# receiver_mega8.net
KiCad netlist of a schematic drawn in EAGLE
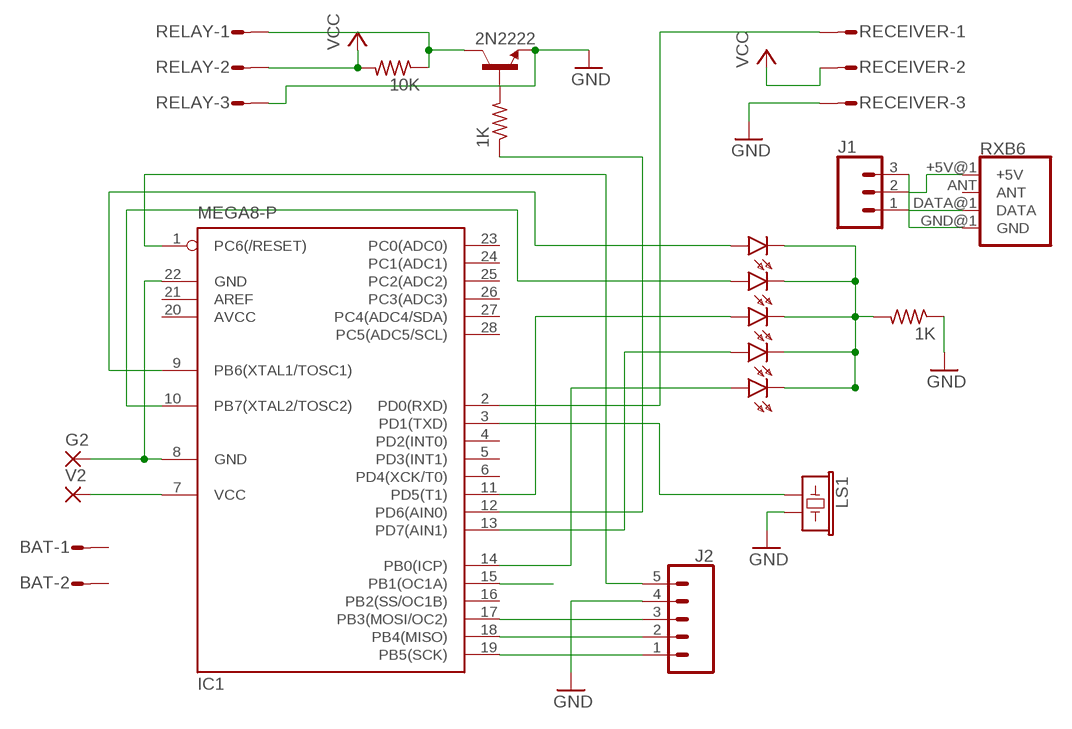
[diagram p0: schematic, sheet 1]

(export (version "E")
  (design (tool "Eeschema 10.0.6"))
  (components
    (comp (ref "BAT")
      (value "S02P")
      (footprint "eagle-import:S02P")
      (libsource (lib "eagle-import") (part "S02P"))
    )
    (comp (ref "D2")
      (value "HLMP6")
      (footprint "eagle-import:HLMP6")
      (fields (field (name "MF") "AGILENT TECHNOLOGIES") (field (name "MPN") "HLMP-6500"))
      (libsource (lib "eagle-import") (part "HLMP6"))
    )
    (comp (ref "D3")
      (value "HLMP6")
      (footprint "eagle-import:HLMP6")
      (fields (field (name "MF") "AGILENT TECHNOLOGIES") (field (name "MPN") "HLMP-6500"))
      (libsource (lib "eagle-import") (part "HLMP6"))
    )
    (comp (ref "D4")
      (value "HLMP6")
      (footprint "eagle-import:HLMP6")
      (fields (field (name "MF") "AGILENT TECHNOLOGIES") (field (name "MPN") "HLMP-6500"))
      (libsource (lib "eagle-import") (part "HLMP6"))
    )
    (comp (ref "D5")
      (value "HLMP6")
      (footprint "eagle-import:HLMP6")
      (fields (field (name "MF") "AGILENT TECHNOLOGIES") (field (name "MPN") "HLMP-6500"))
      (libsource (lib "eagle-import") (part "HLMP6"))
    )
    (comp (ref "D6")
      (value "HLMP6")
      (footprint "eagle-import:HLMP6")
      (fields (field (name "MF") "AGILENT TECHNOLOGIES") (field (name "MPN") "HLMP-6500"))
      (libsource (lib "eagle-import") (part "HLMP6"))
    )
    (comp (ref "G2")
      (value "1,6/0,8")
      (footprint "eagle-import:1,6_0,8")
      (libsource (lib "eagle-import") (part "1,6/0,8"))
    )
    (comp (ref "IC1")
      (value "MEGA8-P")
      (footprint "eagle-import:DIL28-3")
      (libsource (lib "eagle-import") (part "MEGA8-P"))
    )
    (comp (ref "J1")
      (value "CONN_03")
      (footprint "eagle-import:1X03")
      (libsource (lib "eagle-import") (part "CONN_03"))
    )
    (comp (ref "J2")
      (value "CONN_05")
      (footprint "eagle-import:1X05")
      (libsource (lib "eagle-import") (part "CONN_05"))
    )
    (comp (ref "LS1")
      (value "BUZZER-PTH_KIT")
      (footprint "eagle-import:BUZZER-12MM-KIT")
      (libsource (lib "eagle-import") (part "BUZZER-PTH_KIT"))
    )
    (comp (ref "R1")
      (value "1K")
      (footprint "eagle-import:0207_12")
      (libsource (lib "eagle-import") (part "R-US_0207/12"))
    )
    (comp (ref "R2")
      (value "1K")
      (footprint "eagle-import:0207_12")
      (libsource (lib "eagle-import") (part "R-US_0207/12"))
    )
    (comp (ref "R5")
      (value "10K")
      (footprint "eagle-import:0207_12")
      (libsource (lib "eagle-import") (part "R-US_0207/12"))
    )
    (comp (ref "RECEIVER")
      (value "S03P")
      (footprint "eagle-import:S03P")
      (libsource (lib "eagle-import") (part "S03P"))
    )
    (comp (ref "RELAY")
      (value "S03P")
      (footprint "eagle-import:S03P")
      (libsource (lib "eagle-import") (part "S03P"))
    )
    (comp (ref "RXB6")
      (value "RF-LINK_RX")
      (footprint "eagle-import:RF-LINK_RX")
      (libsource (lib "eagle-import") (part "RF-LINK_RX"))
    )
    (comp (ref "T1")
      (value "2N2222")
      (footprint "eagle-import:TO92-CBE")
      (libsource (lib "eagle-import") (part "-NPN-TO92-CBE2N4124"))
    )
    (comp (ref "V2")
      (value "1,6/0,8")
      (footprint "eagle-import:1,6_0,8")
      (libsource (lib "eagle-import") (part "1,6/0,8"))
    )
  )
  (nets
    (net (code "1") (name "/AVCC") (class "Default")
      (node (ref "IC1") (pin "20") (pinfunction "AVCC_20") (pintype "power_in"))
    )
    (net (code "2") (name "GND") (class "Default")
      (node (ref "J2") (pin "4") (pinfunction "4_4") (pintype "passive"))
      (node (ref "LS1") (pin "-") (pinfunction "2_-") (pintype "passive"))
      (node (ref "R2") (pin "1") (pinfunction "1_1") (pintype "passive"))
      (node (ref "RECEIVER") (pin "3") (pinfunction "S_3") (pintype "passive"))
      (node (ref "RELAY") (pin "3") (pinfunction "S_3") (pintype "passive"))
      (node (ref "T1") (pin "E") (pinfunction "E_E") (pintype "passive"))
    )
    (net (code "3") (name "Net-(D2-PadK)") (class "Default")
      (node (ref "D2") (pin "K") (pinfunction "K_K") (pintype "passive"))
      (node (ref "D3") (pin "K") (pinfunction "K_K") (pintype "passive"))
      (node (ref "D4") (pin "K") (pinfunction "K_K") (pintype "passive"))
      (node (ref "D5") (pin "K") (pinfunction "K_K") (pintype "passive"))
      (node (ref "D6") (pin "K") (pinfunction "K_K") (pintype "passive"))
      (node (ref "R2") (pin "2") (pinfunction "2_2") (pintype "passive"))
    )
    (net (code "4") (name "Net-(G2-P)") (class "Default")
      (node (ref "G2") (pin "1") (pinfunction "P_1") (pintype "passive"))
      (node (ref "IC1") (pin "22") (pinfunction "GND_22") (pintype "power_in"))
      (node (ref "IC1") (pin "8") (pinfunction "GND_8") (pintype "power_in"))
    )
    (net (code "5") (name "Net-(IC1-PB0(ICP))") (class "Default")
      (node (ref "D2") (pin "A") (pinfunction "A_A") (pintype "passive"))
      (node (ref "IC1") (pin "14") (pinfunction "PB0(ICP)_14") (pintype "bidirectional"))
    )
    (net (code "6") (name "Net-(IC1-PB3(MOSI{slash}OC2))") (class "Default")
      (node (ref "IC1") (pin "17") (pinfunction "PB3(MOSI/OC2)_17") (pintype "bidirectional"))
      (node (ref "J2") (pin "3") (pinfunction "3_3") (pintype "passive"))
    )
    (net (code "7") (name "Net-(IC1-PB4(MISO))") (class "Default")
      (node (ref "IC1") (pin "18") (pinfunction "PB4(MISO)_18") (pintype "bidirectional"))
      (node (ref "J2") (pin "2") (pinfunction "2_2") (pintype "passive"))
    )
    (net (code "8") (name "Net-(IC1-PB5(SCK))") (class "Default")
      (node (ref "IC1") (pin "19") (pinfunction "PB5(SCK)_19") (pintype "bidirectional"))
      (node (ref "J2") (pin "1") (pinfunction "1_1") (pintype "passive"))
    )
    (net (code "9") (name "Net-(IC1-PB6(XTAL1{slash}TOSC1))") (class "Default")
      (node (ref "D6") (pin "A") (pinfunction "A_A") (pintype "passive"))
      (node (ref "IC1") (pin "9") (pinfunction "PB6(XTAL1/TOSC1)_9") (pintype "bidirectional"))
    )
    (net (code "10") (name "Net-(IC1-PB7(XTAL2{slash}TOSC2))") (class "Default")
      (node (ref "D5") (pin "A") (pinfunction "A_A") (pintype "passive"))
      (node (ref "IC1") (pin "10") (pinfunction "PB7(XTAL2/TOSC2)_10") (pintype "bidirectional"))
    )
    (net (code "11") (name "Net-(IC1-PC6({slash}RESET))") (class "Default")
      (node (ref "IC1") (pin "1") (pinfunction "PC6(/RESET)_1") (pintype "bidirectional"))
      (node (ref "J2") (pin "5") (pinfunction "5_5") (pintype "passive"))
    )
    (net (code "12") (name "Net-(IC1-PD0(RXD))") (class "Default")
      (node (ref "IC1") (pin "2") (pinfunction "PD0(RXD)_2") (pintype "bidirectional"))
      (node (ref "RECEIVER") (pin "1") (pinfunction "S_1") (pintype "passive"))
    )
    (net (code "13") (name "Net-(IC1-PD1(TXD))") (class "Default")
      (node (ref "IC1") (pin "3") (pinfunction "PD1(TXD)_3") (pintype "bidirectional"))
      (node (ref "LS1") (pin "+") (pinfunction "1_+") (pintype "passive"))
    )
    (net (code "14") (name "Net-(IC1-PD5(T1))") (class "Default")
      (node (ref "D4") (pin "A") (pinfunction "A_A") (pintype "passive"))
      (node (ref "IC1") (pin "11") (pinfunction "PD5(T1)_11") (pintype "bidirectional"))
    )
    (net (code "15") (name "Net-(IC1-PD6(AIN0))") (class "Default")
      (node (ref "IC1") (pin "12") (pinfunction "PD6(AIN0)_12") (pintype "bidirectional"))
      (node (ref "R1") (pin "1") (pinfunction "1_1") (pintype "passive"))
    )
    (net (code "16") (name "Net-(IC1-PD7(AIN1))") (class "Default")
      (node (ref "D3") (pin "A") (pinfunction "A_A") (pintype "passive"))
      (node (ref "IC1") (pin "13") (pinfunction "PD7(AIN1)_13") (pintype "bidirectional"))
    )
    (net (code "17") (name "Net-(IC1-VCC)") (class "Default")
      (node (ref "IC1") (pin "7") (pinfunction "VCC_7") (pintype "power_in"))
      (node (ref "V2") (pin "1") (pinfunction "P_1") (pintype "passive"))
    )
    (net (code "18") (name "Net-(R1-Pad2)") (class "Default")
      (node (ref "R1") (pin "2") (pinfunction "2_2") (pintype "passive"))
      (node (ref "T1") (pin "B") (pinfunction "B_B") (pintype "passive"))
    )
    (net (code "19") (name "Net-(RELAYA-S)") (class "Default")
      (node (ref "R5") (pin "1") (pinfunction "1_1") (pintype "passive"))
      (node (ref "RELAY") (pin "1") (pinfunction "S_1") (pintype "passive"))
      (node (ref "T1") (pin "C") (pinfunction "C_C") (pintype "passive"))
    )
    (net (code "20") (name "Net-(RXB6-+5V)") (class "Default")
      (node (ref "J1") (pin "2") (pinfunction "2_2") (pintype "passive"))
      (node (ref "RXB6") (pin "+5V@1") (pinfunction "+5V_+5V@1") (pintype "power_in"))
    )
    (net (code "21") (name "Net-(RXB6-DATA)") (class "Default")
      (node (ref "J1") (pin "1") (pinfunction "1_1") (pintype "passive"))
      (node (ref "RXB6") (pin "DATA@1") (pinfunction "DATA_DATA@1") (pintype "input"))
    )
    (net (code "22") (name "Net-(RXB6-GND)") (class "Default")
      (node (ref "J1") (pin "3") (pinfunction "3_3") (pintype "passive"))
      (node (ref "RXB6") (pin "GND@1") (pinfunction "GND_GND@1") (pintype "power_in"))
    )
    (net (code "23") (name "VCC") (class "Default")
      (node (ref "R5") (pin "2") (pinfunction "2_2") (pintype "passive"))
      (node (ref "RECEIVER") (pin "2") (pinfunction "S_2") (pintype "passive"))
      (node (ref "RELAY") (pin "2") (pinfunction "S_2") (pintype "passive"))
    )
    (net (code "24") (name "unconnected-(BATA-S-Pad1)") (class "Default")
      (node (ref "BAT") (pin "1") (pinfunction "S_1") (pintype "passive"))
    )
    (net (code "25") (name "unconnected-(BATB-S-Pad2)") (class "Default")
      (node (ref "BAT") (pin "2") (pinfunction "S_2") (pintype "passive"))
    )
    (net (code "26") (name "unconnected-(IC1-AREF-Pad21)") (class "Default")
      (node (ref "IC1") (pin "21") (pinfunction "AREF_21") (pintype "passive"))
    )
    (net (code "27") (name "unconnected-(IC1-PB1(OC1A)-Pad15)") (class "Default")
      (node (ref "IC1") (pin "15") (pinfunction "PB1(OC1A)_15") (pintype "bidirectional"))
    )
    (net (code "28") (name "unconnected-(IC1-PB2(SS{slash}OC1B)-Pad16)") (class "Default")
      (node (ref "IC1") (pin "16") (pinfunction "PB2(SS/OC1B)_16") (pintype "bidirectional"))
    )
    (net (code "29") (name "unconnected-(IC1-PC0(ADC0)-Pad23)") (class "Default")
      (node (ref "IC1") (pin "23") (pinfunction "PC0(ADC0)_23") (pintype "bidirectional"))
    )
    (net (code "30") (name "unconnected-(IC1-PC1(ADC1)-Pad24)") (class "Default")
      (node (ref "IC1") (pin "24") (pinfunction "PC1(ADC1)_24") (pintype "bidirectional"))
    )
    (net (code "31") (name "unconnected-(IC1-PC2(ADC2)-Pad25)") (class "Default")
      (node (ref "IC1") (pin "25") (pinfunction "PC2(ADC2)_25") (pintype "bidirectional"))
    )
    (net (code "32") (name "unconnected-(IC1-PC3(ADC3)-Pad26)") (class "Default")
      (node (ref "IC1") (pin "26") (pinfunction "PC3(ADC3)_26") (pintype "bidirectional"))
    )
    (net (code "33") (name "unconnected-(IC1-PC4(ADC4{slash}SDA)-Pad27)") (class "Default")
      (node (ref "IC1") (pin "27") (pinfunction "PC4(ADC4/SDA)_27") (pintype "bidirectional"))
    )
    (net (code "34") (name "unconnected-(IC1-PC5(ADC5{slash}SCL)-Pad28)") (class "Default")
      (node (ref "IC1") (pin "28") (pinfunction "PC5(ADC5/SCL)_28") (pintype "bidirectional"))
    )
    (net (code "35") (name "unconnected-(IC1-PD2(INT0)-Pad4)") (class "Default")
      (node (ref "IC1") (pin "4") (pinfunction "PD2(INT0)_4") (pintype "bidirectional"))
    )
    (net (code "36") (name "unconnected-(IC1-PD3(INT1)-Pad5)") (class "Default")
      (node (ref "IC1") (pin "5") (pinfunction "PD3(INT1)_5") (pintype "bidirectional"))
    )
    (net (code "37") (name "unconnected-(IC1-PD4(XCK{slash}T0)-Pad6)") (class "Default")
      (node (ref "IC1") (pin "6") (pinfunction "PD4(XCK/T0)_6") (pintype "bidirectional"))
    )
    (net (code "38") (name "unconnected-(RXB6-PadANT)") (class "Default")
      (node (ref "RXB6") (pin "ANT") (pinfunction "ANT_ANT") (pintype "passive"))
    )
  )
)
